# ESP32.net
KiCad netlist of a schematic drawn in Altium Designer
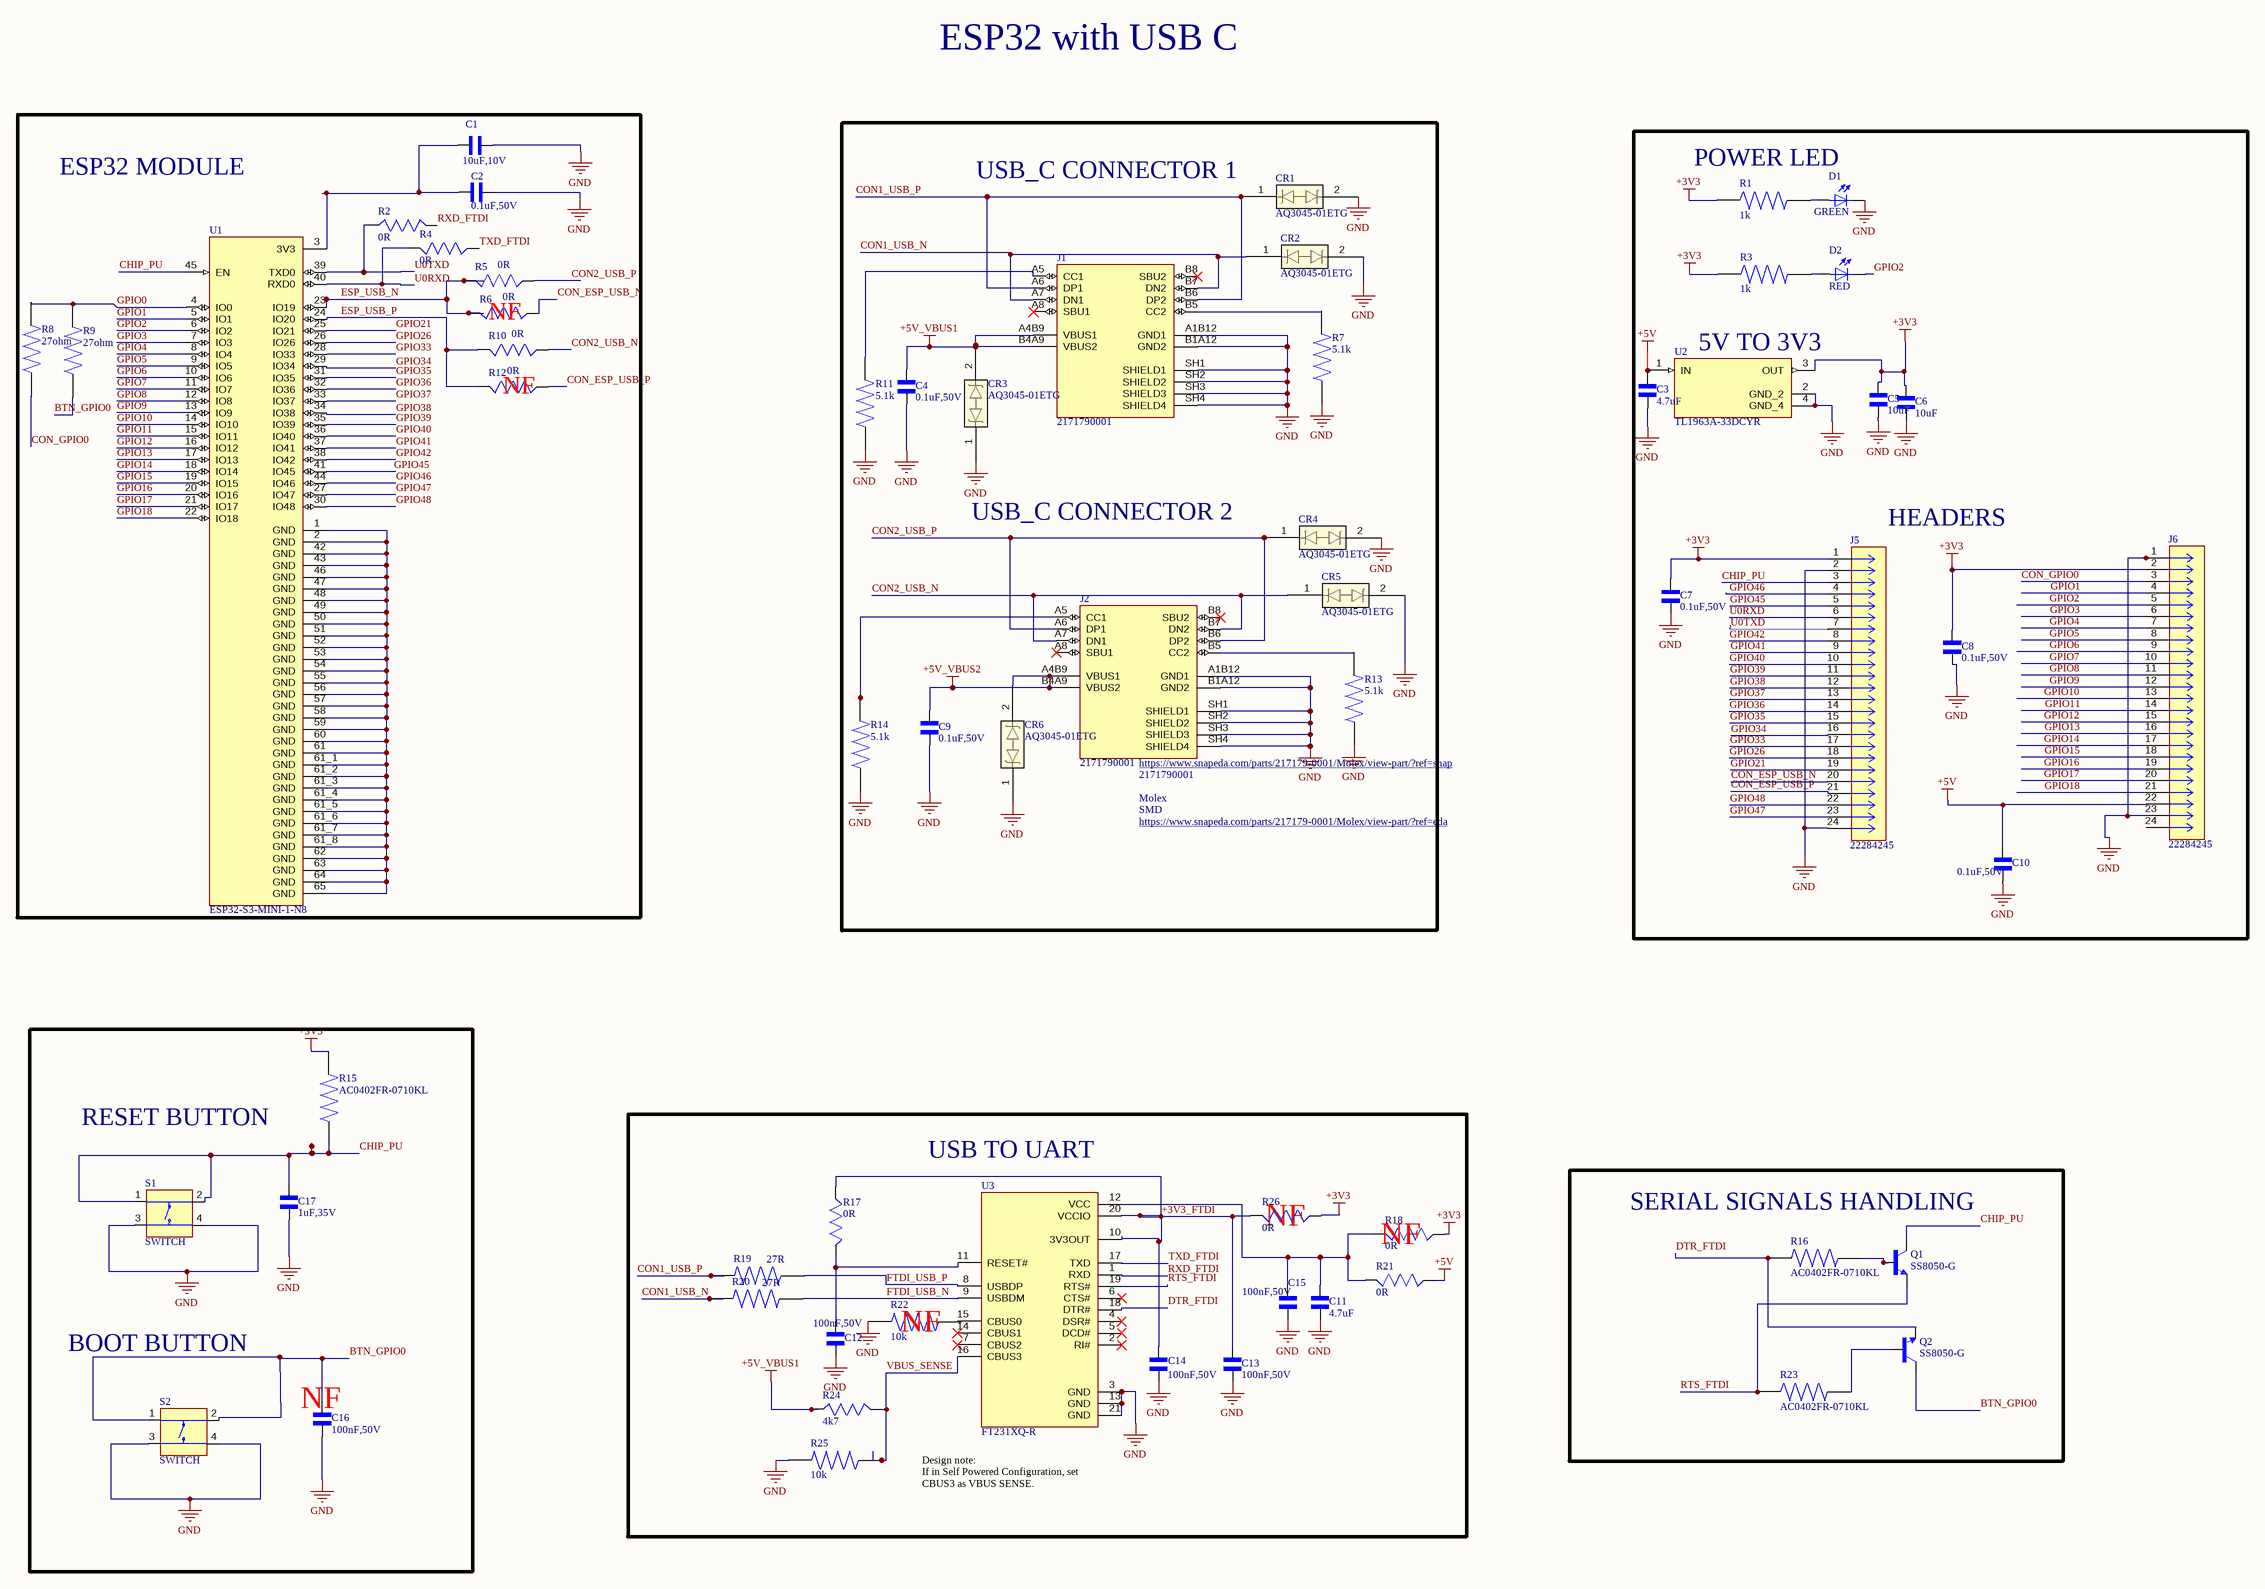
[diagram p0: ESP32.SchDoc]

(export (version "E")
  (design (tool "Eeschema 10.0.6"))
  (components
    (comp (ref "C1")
      (value "10uF,10V")
      (footprint "CAPC1005X90N")
      (description "10 ÂµF Â±20% 10V Ceramic Capacitor X5R 0402 (1005 Metric)")
      (fields (field (name "MF") "Samsung Electro-Mechanics") (field (name "MP") "CL05A106MP8NUB8"))
      (libsource (lib "") (part "CL05A106MP8NUB8_1"))
    )
    (comp (ref "C2")
      (value "0.1uF,50V")
      (footprint "CAPC1005X55N")
      (description "0.1 ÂµF Â±10% 50V Ceramic Capacitor X7R 0402 (1005 Metric)")
      (fields (field (name "MF") "Samsung Electro-Mechanics") (field (name "MP") "CL05B104KB5NNNC"))
      (libsource (lib "") (part "CL05B104KB5NNNC_1"))
    )
    (comp (ref "C3")
      (value "4.7uF")
      (footprint "CAPC1005X55N")
      (description "4.7 ÂµF Â±20% 16V Ceramic Capacitor X5R 0402 (1005 Metric)")
      (fields (field (name "MF") "Samsung Electro-Mechanics") (field (name "MP") "CL05A475MO5LUNC"))
      (libsource (lib "47uF") (part "CL05A475MO5LUNC"))
    )
    (comp (ref "C4")
      (value "0.1uF,50V")
      (footprint "CAPC1005X55N")
      (description "0.1 ÂµF Â±10% 50V Ceramic Capacitor X7R 0402 (1005 Metric)")
      (fields (field (name "MF") "Samsung Electro-Mechanics") (field (name "MP") "CL05B104KB5NNNC"))
      (libsource (lib "0.1uF,50V,0402") (part "CL05B104KB5NNNC"))
    )
    (comp (ref "C5")
      (value "10uF")
      (footprint "CAPC1005X90N")
      (description "10 ÂµF Â±20% 10V Ceramic Capacitor X5R 0402 (1005 Metric)")
      (fields (field (name "MF") "Samsung Electro-Mechanics") (field (name "MP") "CL05A106MP8NUB8"))
      (libsource (lib "10uF,10V,0402") (part "CL05A106MP8NUB8"))
    )
    (comp (ref "C6")
      (value "10uF")
      (footprint "CAPC1005X90N")
      (description "10 ÂµF Â±20% 10V Ceramic Capacitor X5R 0402 (1005 Metric)")
      (fields (field (name "MF") "Samsung Electro-Mechanics") (field (name "MP") "CL05A106MP8NUB8"))
      (libsource (lib "10uF,10V,0402") (part "CL05A106MP8NUB8"))
    )
    (comp (ref "C7")
      (value "0.1uF,50V")
      (footprint "CAPC1005X55N")
      (description "0.1 ÂµF Â±10% 50V Ceramic Capacitor X7R 0402 (1005 Metric)")
      (fields (field (name "MF") "Samsung Electro-Mechanics") (field (name "MP") "CL05B104KB5NNNC"))
      (libsource (lib "0.1uF,50V,0402") (part "CL05B104KB5NNNC"))
    )
    (comp (ref "C8")
      (value "0.1uF,50V")
      (footprint "CAPC1005X55N")
      (description "0.1 ÂµF Â±10% 50V Ceramic Capacitor X7R 0402 (1005 Metric)")
      (fields (field (name "MF") "Samsung Electro-Mechanics") (field (name "MP") "CL05B104KB5NNNC"))
      (libsource (lib "0.1uF,50V,0402") (part "CL05B104KB5NNNC"))
    )
    (comp (ref "C9")
      (value "0.1uF,50V")
      (footprint "CAPC1005X55N")
      (description "0.1 ÂµF Â±10% 50V Ceramic Capacitor X7R 0402 (1005 Metric)")
      (fields (field (name "MF") "Samsung Electro-Mechanics") (field (name "MP") "CL05B104KB5NNNC"))
      (libsource (lib "0.1uF,50V,0402") (part "CL05B104KB5NNNC"))
    )
    (comp (ref "C10")
      (value "0.1uF,50V")
      (footprint "CAPC1005X55N")
      (description "0.1 ÂµF Â±10% 50V Ceramic Capacitor X7R 0402 (1005 Metric)")
      (fields (field (name "MF") "Samsung Electro-Mechanics") (field (name "MP") "CL05B104KB5NNNC"))
      (libsource (lib "0.1uF,50V,0402") (part "CL05B104KB5NNNC"))
    )
    (comp (ref "C11")
      (value "4.7uF")
      (footprint "CAPC1005X55N")
      (description "4.7 ÂµF Â±20% 16V Ceramic Capacitor X5R 0402 (1005 Metric)")
      (fields (field (name "MF") "Samsung Electro-Mechanics") (field (name "MP") "CL05A475MO5LUNC"))
      (libsource (lib "47uF") (part "CL05A475MO5LUNC"))
    )
    (comp (ref "C12")
      (value "100nF,50V")
      (footprint "CAPC1005X55N")
      (description "0.1 ÂµF Â±10% 50V Ceramic Capacitor X7R 0402 (1005 Metric)")
      (fields (field (name "MF") "Samsung Electro-Mechanics") (field (name "MP") "CL05B104KB5NNNC"))
      (libsource (lib "0.1uF,50V,0402") (part "CL05B104KB5NNNC"))
    )
    (comp (ref "C13")
      (value "100nF,50V")
      (footprint "CAPC1005X55N")
      (description "0.1 ÂµF Â±10% 50V Ceramic Capacitor X7R 0402 (1005 Metric)")
      (fields (field (name "MF") "Samsung Electro-Mechanics") (field (name "MP") "CL05B104KB5NNNC"))
      (libsource (lib "0.1uF,50V,0402") (part "CL05B104KB5NNNC"))
    )
    (comp (ref "C14")
      (value "100nF,50V")
      (footprint "CAPC1005X55N")
      (description "0.1 ÂµF Â±10% 50V Ceramic Capacitor X7R 0402 (1005 Metric)")
      (fields (field (name "MF") "Samsung Electro-Mechanics") (field (name "MP") "CL05B104KB5NNNC"))
      (libsource (lib "0.1uF,50V,0402") (part "CL05B104KB5NNNC"))
    )
    (comp (ref "C15")
      (value "100nF,50V")
      (footprint "CAPC1005X55N")
      (description "0.1 ÂµF Â±10% 50V Ceramic Capacitor X7R 0402 (1005 Metric)")
      (fields (field (name "MF") "Samsung Electro-Mechanics") (field (name "MP") "CL05B104KB5NNNC"))
      (libsource (lib "0.1uF,50V,0402") (part "CL05B104KB5NNNC"))
    )
    (comp (ref "C16")
      (value "100nF,50V")
      (footprint "CAPC1005X55N")
      (description "0.1 ÂµF Â±10% 50V Ceramic Capacitor X7R 0402 (1005 Metric)")
      (fields (field (name "MF") "Samsung Electro-Mechanics") (field (name "MP") "CL05B104KB5NNNC"))
      (libsource (lib "0.1uF,50V,0402") (part "CL05B104KB5NNNC"))
    )
    (comp (ref "C17")
      (value "1uF,35V")
      (footprint "CAPC1005X65N")
      (description "1 ÂµF Â±10% 35V Ceramic Capacitor X5R 0402 (1005 Metric)")
      (fields (field (name "MF") "Samsung") (field (name "MP") "CL05A105KL5NRNC"))
      (libsource (lib "1uF,35V,0402") (part "CL05A105KL5NRNC"))
    )
    (comp (ref "CR1")
      (value "AQ3045-01ETG")
      (footprint "RTVS_SOD882_LTF")
      (description "Description")
      (fields (field (name "COPYRIGHT") "Copyright (C) 2025 Ultra Librarian. All rights reserved."))
      (libsource (lib "AQ3045-01ETG") (part "AQ3045-01ETG"))
    )
    (comp (ref "CR2")
      (value "AQ3045-01ETG")
      (footprint "RTVS_SOD882_LTF")
      (description "Description")
      (fields (field (name "COPYRIGHT") "Copyright (C) 2025 Ultra Librarian. All rights reserved."))
      (libsource (lib "AQ3045-01ETG") (part "AQ3045-01ETG"))
    )
    (comp (ref "CR3")
      (value "AQ3045-01ETG")
      (footprint "RTVS_SOD882_LTF")
      (description "Description")
      (fields (field (name "COPYRIGHT") "Copyright (C) 2025 Ultra Librarian. All rights reserved."))
      (libsource (lib "") (part "AQ3045-01ETG_1"))
    )
    (comp (ref "CR4")
      (value "AQ3045-01ETG")
      (footprint "RTVS_SOD882_LTF")
      (description "Description")
      (fields (field (name "COPYRIGHT") "Copyright (C) 2025 Ultra Librarian. All rights reserved."))
      (libsource (lib "AQ3045-01ETG") (part "AQ3045-01ETG"))
    )
    (comp (ref "CR5")
      (value "AQ3045-01ETG")
      (footprint "RTVS_SOD882_LTF")
      (description "Description")
      (fields (field (name "COPYRIGHT") "Copyright (C) 2025 Ultra Librarian. All rights reserved."))
      (libsource (lib "AQ3045-01ETG") (part "AQ3045-01ETG"))
    )
    (comp (ref "CR6")
      (value "AQ3045-01ETG")
      (footprint "RTVS_SOD882_LTF")
      (description "Description")
      (fields (field (name "COPYRIGHT") "Copyright (C) 2025 Ultra Librarian. All rights reserved."))
      (libsource (lib "") (part "AQ3045-01ETG_1"))
    )
    (comp (ref "D1")
      (value "GREEN")
      (footprint "LEDC1005X35N")
      (description "Yellow-Green 571nm LED Indication - Discrete 2V 0402 (1005 Metric)")
      (fields (field (name "MF") "Vishay") (field (name "MP") "VLMG1500-GS08"))
      (libsource (lib "GREEN LED") (part "VLMG1500-GS08"))
    )
    (comp (ref "D2")
      (value "RED")
      (footprint "LEDC1005X35N")
      (description "Yellow-Green 571nm LED Indication - Discrete 2V 0402 (1005 Metric)")
      (fields (field (name "MF") "Vishay") (field (name "MP") "VLMG1500-GS08"))
      (libsource (lib "GREEN LED") (part "VLMG1500-GS08"))
    )
    (comp (ref "J1")
      (value "2171790001")
      (footprint "MOLEX_2171790001")
      (description "USB Type C - Connector, Top-mount SMT, 16pos ¦ Molex Incorporated 217179-0001")
      (fields (field (name "JLCPCB PART #") "C3197684") (field (name "MANUFACTURER") "Molex"))
      (libsource (lib "USB C") (part "2171790001"))
    )
    (comp (ref "J2")
      (value "2171790001")
      (footprint "MOLEX_2171790001")
      (description "USB Type C - Connector, Top-mount SMT, 16pos ¦ Molex Incorporated 217179-0001")
      (fields
        (field (name "SNAPEDA_LINK") "https://www.snapeda.com/parts/217179-0001/Molex/view-part/?ref=snap")
        (field (name "MANUFACTURER PART #") "2171790001")
        (field (name "JLCPCB PART #") "C3197684")
        (field (name "MANUFACTURER") "Molex")
        (field (name "PACKAGE") "SMD")
        (field (name "CHECK_PRICES") "https://www.snapeda.com/parts/217179-0001/Molex/view-part/?ref=eda")
      )
      (libsource (lib "USB C") (part "2171790001"))
    )
    (comp (ref "J5")
      (value "22284245")
      (footprint "CONN_SD-42375-001_M295_24_MOL")
      (description "Connector Header Through Hole 24 position 0.100 (2.54mm)")
      (fields (field (name "MF") "Molex") (field (name "MP") "22-28-4245"))
      (libsource (lib "24 PIN HEADERS") (part "22284245"))
    )
    (comp (ref "J6")
      (value "22284245")
      (footprint "CONN_SD-42375-001_M295_24_MOL")
      (description "Connector Header Through Hole 24 position 0.100 (2.54mm)")
      (fields (field (name "MF") "Molex") (field (name "MP") "22-28-4245"))
      (libsource (lib "24 PIN HEADERS") (part "22284245"))
    )
    (comp (ref "Q1")
      (value "SS8050-G")
      (footprint "TRANS_SS8050-G")
      (description "Bipolar (BJT) Transistor NPN 25 V 1.5 A 100MHz 300 mW Surface Mount SOT-23-3")
      (fields (field (name "DIGI-KEY_PART_NUMBER") "641-1790-2-ND") (field (name "MP") "SS8050G"))
      (libsource (lib "") (part "SS8050-G_1"))
    )
    (comp (ref "Q2")
      (value "SS8050-G")
      (footprint "TRANS_SS8050-G")
      (description "Bipolar (BJT) Transistor NPN 25 V 1.5 A 100MHz 300 mW Surface Mount SOT-23-3")
      (fields (field (name "DIGI-KEY_PART_NUMBER") "641-1790-2-ND") (field (name "MP") "SS8050G"))
      (libsource (lib "SS8050-G") (part "SS8050-G"))
    )
    (comp (ref "R1")
      (value "1k")
      (footprint "RESC1005X40N")
      (description "1 kOhms Â±1% 0.063W, 1/16W Chip Resistor 0402 (1005 Metric) Moisture Resistant Thick Film")
      (fields (field (name "MF") "Yageo Corporation") (field (name "MP") "RC0402FR071KL"))
      (libsource (lib "1kR") (part "RC0402FR-071KL"))
    )
    (comp (ref "R2")
      (value "0R")
      (footprint "RESC1005X40")
      (description "0 Ohms Jumper 0.063W, 1/16W Chip Resistor 0402 (1005 Metric) Moisture Resistant Thick Film")
      (fields (field (name "MF") "Yageo") (field (name "DIGI-KEY_PART_NUMBER") "311-0.0JRTR-ND"))
      (libsource (lib "0R") (part "RC0402JR-070RL"))
    )
    (comp (ref "R3")
      (value "1k")
      (footprint "RESC1005X40N")
      (description "1 kOhms Â±1% 0.063W, 1/16W Chip Resistor 0402 (1005 Metric) Moisture Resistant Thick Film")
      (fields (field (name "MF") "Yageo Corporation") (field (name "MP") "RC0402FR071KL"))
      (libsource (lib "1kR") (part "RC0402FR-071KL"))
    )
    (comp (ref "R4")
      (value "0R")
      (footprint "RESC1005X40")
      (description "0 Ohms Jumper 0.063W, 1/16W Chip Resistor 0402 (1005 Metric) Moisture Resistant Thick Film")
      (fields (field (name "MF") "Yageo") (field (name "DIGI-KEY_PART_NUMBER") "311-0.0JRTR-ND"))
      (libsource (lib "0R") (part "RC0402JR-070RL"))
    )
    (comp (ref "R5")
      (value "0R")
      (footprint "RESC1005X40")
      (description "0 Ohms Jumper 0.063W, 1/16W Chip Resistor 0402 (1005 Metric) Moisture Resistant Thick Film")
      (fields (field (name "MF") "Yageo") (field (name "DIGI-KEY_PART_NUMBER") "311-0.0JRTR-ND"))
      (libsource (lib "0R") (part "RC0402JR-070RL"))
    )
    (comp (ref "R6")
      (value "0R")
      (footprint "RESC1005X40")
      (description "0 Ohms Jumper 0.063W, 1/16W Chip Resistor 0402 (1005 Metric) Moisture Resistant Thick Film")
      (fields (field (name "MF") "Yageo") (field (name "DIGI-KEY_PART_NUMBER") "311-0.0JRTR-ND"))
      (libsource (lib "0R") (part "RC0402JR-070RL"))
    )
    (comp (ref "R7")
      (value "5.1k")
      (footprint "RESC1005X40N")
      (description "27 Ohms Â±1% 0.063W, 1/16W Chip Resistor 0402 (1005 Metric) Moisture Resistant Thick Film")
      (fields (field (name "MF") "Yageo") (field (name "MP") "RC0402FR-0727RL"))
      (libsource (lib "5.1k Ohm (2)") (part "RC0402FR-0727RL"))
    )
    (comp (ref "R8")
      (value "27ohm")
      (footprint "RESC1005X40N")
      (description "27 Ohms Â±1% 0.063W, 1/16W Chip Resistor 0402 (1005 Metric) Moisture Resistant Thick Film")
      (fields (field (name "MF") "Yageo") (field (name "MP") "RC0402FR-0727RL"))
      (libsource (lib "27ohm,0402") (part "RC0402FR-0727RL"))
    )
    (comp (ref "R9")
      (value "27ohm")
      (footprint "RESC1005X40N")
      (description "27 Ohms Â±1% 0.063W, 1/16W Chip Resistor 0402 (1005 Metric) Moisture Resistant Thick Film")
      (fields (field (name "MF") "Yageo") (field (name "MP") "RC0402FR-0727RL"))
      (libsource (lib "27ohm,0402") (part "RC0402FR-0727RL"))
    )
    (comp (ref "R10")
      (value "0R")
      (footprint "RESC1005X40")
      (description "0 Ohms Jumper 0.063W, 1/16W Chip Resistor 0402 (1005 Metric) Moisture Resistant Thick Film")
      (fields (field (name "MF") "Yageo") (field (name "DIGI-KEY_PART_NUMBER") "311-0.0JRTR-ND"))
      (libsource (lib "0R") (part "RC0402JR-070RL"))
    )
    (comp (ref "R11")
      (value "5.1k")
      (footprint "RESC1005X40N")
      (description "27 Ohms Â±1% 0.063W, 1/16W Chip Resistor 0402 (1005 Metric) Moisture Resistant Thick Film")
      (fields (field (name "MF") "Yageo") (field (name "MP") "RC0402FR-0727RL"))
      (libsource (lib "5.1k Ohm (2)") (part "RC0402FR-0727RL"))
    )
    (comp (ref "R12")
      (value "0R")
      (footprint "RESC1005X40")
      (description "0 Ohms Jumper 0.063W, 1/16W Chip Resistor 0402 (1005 Metric) Moisture Resistant Thick Film")
      (fields (field (name "MF") "Yageo") (field (name "DIGI-KEY_PART_NUMBER") "311-0.0JRTR-ND"))
      (libsource (lib "0R") (part "RC0402JR-070RL"))
    )
    (comp (ref "R13")
      (value "5.1k")
      (footprint "RESC1005X40N")
      (description "27 Ohms Â±1% 0.063W, 1/16W Chip Resistor 0402 (1005 Metric) Moisture Resistant Thick Film")
      (fields (field (name "MF") "Yageo") (field (name "MP") "RC0402FR-0727RL"))
      (libsource (lib "5.1k Ohm (2)") (part "RC0402FR-0727RL"))
    )
    (comp (ref "R14")
      (value "5.1k")
      (footprint "RESC1005X40N")
      (description "27 Ohms Â±1% 0.063W, 1/16W Chip Resistor 0402 (1005 Metric) Moisture Resistant Thick Film")
      (fields (field (name "MF") "Yageo") (field (name "MP") "RC0402FR-0727RL"))
      (libsource (lib "5.1k Ohm (2)") (part "RC0402FR-0727RL"))
    )
    (comp (ref "R15")
      (value "AC0402FR-0710KL")
      (footprint "RESC1005X37N")
      (fields (field (name "DIGI-KEY_PART_NUMBER") "YAG3436TR-ND") (field (name "MF") "Yageo"))
      (libsource (lib "10k ohm") (part "AC0402FR-0710KL"))
    )
    (comp (ref "R16")
      (value "AC0402FR-0710KL")
      (footprint "RESC1005X37N")
      (fields (field (name "DIGI-KEY_PART_NUMBER") "YAG3436TR-ND") (field (name "MF") "Yageo"))
      (libsource (lib "10k ohm") (part "AC0402FR-0710KL"))
    )
    (comp (ref "R17")
      (value "0R")
      (footprint "RESC1005X40")
      (description "0 Ohms Jumper 0.063W, 1/16W Chip Resistor 0402 (1005 Metric) Moisture Resistant Thick Film")
      (fields (field (name "MF") "Yageo") (field (name "DIGI-KEY_PART_NUMBER") "311-0.0JRTR-ND"))
      (libsource (lib "0R") (part "RC0402JR-070RL"))
    )
    (comp (ref "R18")
      (value "0R")
      (footprint "RESC1005X40")
      (description "0 Ohms Jumper 0.063W, 1/16W Chip Resistor 0402 (1005 Metric) Moisture Resistant Thick Film")
      (fields (field (name "MF") "Yageo") (field (name "DIGI-KEY_PART_NUMBER") "311-0.0JRTR-ND"))
      (libsource (lib "0R") (part "RC0402JR-070RL"))
    )
    (comp (ref "R19")
      (value "27R")
      (footprint "RESC1005X40N")
      (description "27 Ohms Â±1% 0.063W, 1/16W Chip Resistor 0402 (1005 Metric) Moisture Resistant Thick Film")
      (fields (field (name "MF") "Yageo") (field (name "MP") "RC0402FR-0727RL"))
      (libsource (lib "27ohm,0402") (part "RC0402FR-0727RL"))
    )
    (comp (ref "R20")
      (value "27R")
      (footprint "RESC1005X40N")
      (description "27 Ohms Â±1% 0.063W, 1/16W Chip Resistor 0402 (1005 Metric) Moisture Resistant Thick Film")
      (fields (field (name "MF") "Yageo") (field (name "MP") "RC0402FR-0727RL"))
      (libsource (lib "27ohm,0402") (part "RC0402FR-0727RL"))
    )
    (comp (ref "R21")
      (value "0R")
      (footprint "RESC1005X40")
      (description "0 Ohms Jumper 0.063W, 1/16W Chip Resistor 0402 (1005 Metric) Moisture Resistant Thick Film")
      (fields (field (name "MF") "Yageo") (field (name "DIGI-KEY_PART_NUMBER") "311-0.0JRTR-ND"))
      (libsource (lib "0R") (part "RC0402JR-070RL"))
    )
    (comp (ref "R22")
      (value "10k")
      (footprint "RESC1005X37N")
      (fields
        (field (name "MP") "AC0402FR-0710KL")
        (field (name "DIGI-KEY_PART_NUMBER") "YAG3436TR-ND")
        (field (name "MF") "Yageo")
      )
      (libsource (lib "10k ohm") (part "AC0402FR-0710KL"))
    )
    (comp (ref "R23")
      (value "AC0402FR-0710KL")
      (footprint "RESC1005X37N")
      (fields (field (name "DIGI-KEY_PART_NUMBER") "YAG3436TR-ND") (field (name "MF") "Yageo"))
      (libsource (lib "10k ohm") (part "AC0402FR-0710KL"))
    )
    (comp (ref "R24")
      (value "4k7")
      (footprint "RESC1005X40")
      (description "4.7 kOhms Â±1% 0.063W, 1/16W Chip Resistor 0402 (1005 Metric) Moisture Resistant Thick Film")
      (fields (field (name "MF") "Yageo") (field (name "MP") "RC0402FR-074K7L"))
      (libsource (lib "4.7k ohm") (part "RC0402FR-074K7L"))
    )
    (comp (ref "R25")
      (value "10k")
      (footprint "RESC1005X37N")
      (fields
        (field (name "MP") "AC0402FR-0710KL")
        (field (name "DIGI-KEY_PART_NUMBER") "YAG3436TR-ND")
        (field (name "MF") "Yageo")
      )
      (libsource (lib "10k ohm") (part "AC0402FR-0710KL"))
    )
    (comp (ref "R26")
      (value "0R")
      (footprint "RESC1005X40")
      (description "0 Ohms Jumper 0.063W, 1/16W Chip Resistor 0402 (1005 Metric) Moisture Resistant Thick Film")
      (fields (field (name "MF") "Yageo") (field (name "DIGI-KEY_PART_NUMBER") "311-0.0JRTR-ND"))
      (libsource (lib "0R") (part "RC0402JR-070RL"))
    )
    (comp (ref "S1")
      (value "SWITCH")
      (footprint "SWITCH_43SMTR92LFS")
      (fields (field (name "MF") "C&K") (field (name "MP") "PTS645SK50SMTR92 LFS"))
      (libsource (lib "Tactile switch") (part "PTS645SK50SMTR92LFS"))
    )
    (comp (ref "S2")
      (value "SWITCH")
      (footprint "SWITCH_43SMTR92LFS")
      (fields (field (name "MF") "C&K") (field (name "MP") "PTS645SK50SMTR92 LFS"))
      (libsource (lib "Tactile switch") (part "PTS645SK50SMTR92LFS"))
    )
    (comp (ref "U1")
      (value "ESP32-S3-MINI-1-N8")
      (footprint "XCVR_ESP32-S3-MINI-1-N8")
      (fields (field (name "MANUFACTURER") "Espressif Systems") (field (name "JLCPCB PART #") "C2913206"))
      (libsource (lib "ESP32-S3-MINI-1-N8") (part "ESP32-S3-MINI-1-N8"))
    )
    (comp (ref "U2")
      (value "TL1963A-33DCYR")
      (footprint "VREG_TL1963A-33DCYR")
      (description "1.5-A, 20-V, low-dropout voltage regulator with reverse current & reverse voltage protection")
      (fields (field (name "MF") "Texas Instruments"))
      (libsource (lib "LDO") (part "TL1963A-33DCYR"))
    )
    (comp (ref "U3")
      (value "FT231XQ-R")
      (footprint "QFN50P400X400X80-21N")
      (description "USB2.0 Full Speed IC offers a compact bridge to full handshake UART Interface")
      (libsource (lib "USB_to_UART") (part "FT231XQ-R"))
    )
  )
  (nets
    (net (code "1") (name "+3V3") (class "Default")
      (node (ref "C5") (pin "2") (pinfunction "2_2") (pintype "passive"))
      (node (ref "C6") (pin "2") (pinfunction "2_2") (pintype "passive"))
      (node (ref "C7") (pin "2") (pinfunction "2_2") (pintype "passive"))
      (node (ref "C8") (pin "2") (pinfunction "2_2") (pintype "passive"))
      (node (ref "J5") (pin "1") (pinfunction "1_1") (pintype "passive"))
      (node (ref "J6") (pin "2") (pinfunction "2_2") (pintype "passive"))
      (node (ref "R1") (pin "1") (pinfunction "1_1") (pintype "passive"))
      (node (ref "R15") (pin "2") (pinfunction "2_2") (pintype "passive"))
      (node (ref "R18") (pin "2") (pinfunction "2_2") (pintype "passive"))
      (node (ref "R26") (pin "2") (pinfunction "2_2") (pintype "passive"))
      (node (ref "R3") (pin "1") (pinfunction "1_1") (pintype "passive"))
      (node (ref "U2") (pin "3") (pinfunction "OUT_3") (pintype "output"))
    )
    (net (code "2") (name "+5V") (class "Default")
      (node (ref "C10") (pin "2") (pinfunction "2_2") (pintype "passive"))
      (node (ref "C3") (pin "2") (pinfunction "2_2") (pintype "passive"))
      (node (ref "J6") (pin "22") (pinfunction "22_22") (pintype "passive"))
      (node (ref "R21") (pin "2") (pinfunction "2_2") (pintype "passive"))
      (node (ref "U2") (pin "1") (pinfunction "IN_1") (pintype "input"))
    )
    (net (code "3") (name "+5V_VBUS1") (class "Default")
      (node (ref "C4") (pin "2") (pinfunction "2_2") (pintype "passive"))
      (node (ref "CR3") (pin "2") (pinfunction "2_2") (pintype "passive"))
      (node (ref "J1") (pin "A4B9") (pinfunction "VBUS1_A4B9") (pintype "power_in"))
      (node (ref "J1") (pin "B4A9") (pinfunction "VBUS2_B4A9") (pintype "power_in"))
      (node (ref "R24") (pin "2") (pinfunction "2_2") (pintype "passive"))
    )
    (net (code "4") (name "+5V_VBUS2") (class "Default")
      (node (ref "C9") (pin "2") (pinfunction "2_2") (pintype "passive"))
      (node (ref "CR6") (pin "2") (pinfunction "2_2") (pintype "passive"))
      (node (ref "J2") (pin "A4B9") (pinfunction "VBUS1_A4B9") (pintype "power_in"))
      (node (ref "J2") (pin "B4A9") (pinfunction "VBUS2_B4A9") (pintype "power_in"))
    )
    (net (code "5") (name "/+3V3_FTDI") (class "Default")
      (node (ref "C13") (pin "2") (pinfunction "2_2") (pintype "passive"))
      (node (ref "C14") (pin "2") (pinfunction "2_2") (pintype "passive"))
      (node (ref "R17") (pin "2") (pinfunction "2_2") (pintype "passive"))
      (node (ref "R26") (pin "1") (pinfunction "1_1") (pintype "passive"))
      (node (ref "U3") (pin "10") (pinfunction "3V3OUT_10") (pintype "passive"))
      (node (ref "U3") (pin "20") (pinfunction "VCCIO_20") (pintype "passive"))
    )
    (net (code "6") (name "/BTN_GPIO0") (class "Default")
      (node (ref "C16") (pin "2") (pinfunction "2_2") (pintype "passive"))
      (node (ref "Q2") (pin "3") (pinfunction "C_3") (pintype "passive"))
      (node (ref "R9") (pin "1") (pinfunction "1_1") (pintype "passive"))
      (node (ref "S2") (pin "1") (pinfunction "1_1") (pintype "passive"))
      (node (ref "S2") (pin "2") (pinfunction "2_2") (pintype "passive"))
    )
    (net (code "7") (name "/CHIP_PU") (class "Default")
      (node (ref "C17") (pin "1") (pinfunction "1_1") (pintype "passive"))
      (node (ref "J5") (pin "3") (pinfunction "3_3") (pintype "passive"))
      (node (ref "Q1") (pin "3") (pinfunction "C_3") (pintype "passive"))
      (node (ref "R15") (pin "1") (pinfunction "1_1") (pintype "passive"))
      (node (ref "S1") (pin "1") (pinfunction "1_1") (pintype "passive"))
      (node (ref "S1") (pin "2") (pinfunction "2_2") (pintype "passive"))
      (node (ref "U1") (pin "45") (pinfunction "EN_45") (pintype "input"))
    )
    (net (code "8") (name "/CON1_USB_N") (class "Default")
      (node (ref "CR2") (pin "1") (pinfunction "1_1") (pintype "passive"))
      (node (ref "J1") (pin "A7") (pinfunction "DN1_A7") (pintype "bidirectional"))
      (node (ref "J1") (pin "B7") (pinfunction "DN2_B7") (pintype "bidirectional"))
      (node (ref "R20") (pin "1") (pinfunction "1_1") (pintype "passive"))
    )
    (net (code "9") (name "/CON1_USB_P") (class "Default")
      (node (ref "CR1") (pin "1") (pinfunction "1_1") (pintype "passive"))
      (node (ref "J1") (pin "A6") (pinfunction "DP1_A6") (pintype "bidirectional"))
      (node (ref "J1") (pin "B6") (pinfunction "DP2_B6") (pintype "bidirectional"))
      (node (ref "R19") (pin "1") (pinfunction "1_1") (pintype "passive"))
    )
    (net (code "10") (name "/CON2_USB_N") (class "Default")
      (node (ref "CR5") (pin "1") (pinfunction "1_1") (pintype "passive"))
      (node (ref "J2") (pin "A7") (pinfunction "DN1_A7") (pintype "bidirectional"))
      (node (ref "J2") (pin "B7") (pinfunction "DN2_B7") (pintype "bidirectional"))
      (node (ref "R10") (pin "2") (pinfunction "2_2") (pintype "passive"))
    )
    (net (code "11") (name "/CON2_USB_P") (class "Default")
      (node (ref "CR4") (pin "1") (pinfunction "1_1") (pintype "passive"))
      (node (ref "J2") (pin "A6") (pinfunction "DP1_A6") (pintype "bidirectional"))
      (node (ref "J2") (pin "B6") (pinfunction "DP2_B6") (pintype "bidirectional"))
      (node (ref "R5") (pin "2") (pinfunction "2_2") (pintype "passive"))
    )
    (net (code "12") (name "/CON_ESP_USB_N") (class "Default")
      (node (ref "J5") (pin "20") (pinfunction "20_20") (pintype "passive"))
      (node (ref "R6") (pin "2") (pinfunction "2_2") (pintype "passive"))
    )
    (net (code "13") (name "/CON_ESP_USB_P") (class "Default")
      (node (ref "J5") (pin "21") (pinfunction "21_21") (pintype "passive"))
      (node (ref "R12") (pin "2") (pinfunction "2_2") (pintype "passive"))
    )
    (net (code "14") (name "/CON_GPIO0") (class "Default")
      (node (ref "J6") (pin "3") (pinfunction "3_3") (pintype "passive"))
      (node (ref "R8") (pin "1") (pinfunction "1_1") (pintype "passive"))
    )
    (net (code "15") (name "/DTR_FTDI") (class "Default")
      (node (ref "Q2") (pin "2") (pinfunction "E_2") (pintype "passive"))
      (node (ref "R16") (pin "1") (pinfunction "1_1") (pintype "passive"))
      (node (ref "U3") (pin "18") (pinfunction "DTR#_18") (pintype "passive"))
    )
    (net (code "16") (name "/ESP_USB_N") (class "Default")
      (node (ref "R5") (pin "1") (pinfunction "1_1") (pintype "passive"))
      (node (ref "R6") (pin "1") (pinfunction "1_1") (pintype "passive"))
      (node (ref "U1") (pin "23") (pinfunction "IO19_23") (pintype "bidirectional"))
    )
    (net (code "17") (name "/ESP_USB_P") (class "Default")
      (node (ref "R10") (pin "1") (pinfunction "1_1") (pintype "passive"))
      (node (ref "R12") (pin "1") (pinfunction "1_1") (pintype "passive"))
      (node (ref "U1") (pin "24") (pinfunction "IO20_24") (pintype "bidirectional"))
    )
    (net (code "18") (name "/FTDI_USB_N") (class "Default")
      (node (ref "R20") (pin "2") (pinfunction "2_2") (pintype "passive"))
      (node (ref "U3") (pin "9") (pinfunction "USBDM_9") (pintype "passive"))
    )
    (net (code "19") (name "/FTDI_USB_P") (class "Default")
      (node (ref "R19") (pin "2") (pinfunction "2_2") (pintype "passive"))
      (node (ref "U3") (pin "8") (pinfunction "USBDP_8") (pintype "passive"))
    )
    (net (code "20") (name "/GPIO0") (class "Default")
      (node (ref "R8") (pin "2") (pinfunction "2_2") (pintype "passive"))
      (node (ref "R9") (pin "2") (pinfunction "2_2") (pintype "passive"))
      (node (ref "U1") (pin "4") (pinfunction "IO0_4") (pintype "bidirectional"))
    )
    (net (code "21") (name "/GPIO1") (class "Default")
      (node (ref "J6") (pin "4") (pinfunction "4_4") (pintype "passive"))
      (node (ref "U1") (pin "5") (pinfunction "IO1_5") (pintype "bidirectional"))
    )
    (net (code "22") (name "/GPIO2") (class "Default")
      (node (ref "D2") (pin "2") (pinfunction "2_2") (pintype "passive"))
      (node (ref "J6") (pin "5") (pinfunction "5_5") (pintype "passive"))
      (node (ref "U1") (pin "6") (pinfunction "IO2_6") (pintype "bidirectional"))
    )
    (net (code "23") (name "/GPIO3") (class "Default")
      (node (ref "J6") (pin "6") (pinfunction "6_6") (pintype "passive"))
      (node (ref "U1") (pin "7") (pinfunction "IO3_7") (pintype "bidirectional"))
    )
    (net (code "24") (name "/GPIO4") (class "Default")
      (node (ref "J6") (pin "7") (pinfunction "7_7") (pintype "passive"))
      (node (ref "U1") (pin "8") (pinfunction "IO4_8") (pintype "bidirectional"))
    )
    (net (code "25") (name "/GPIO5") (class "Default")
      (node (ref "J6") (pin "8") (pinfunction "8_8") (pintype "passive"))
      (node (ref "U1") (pin "9") (pinfunction "IO5_9") (pintype "bidirectional"))
    )
    (net (code "26") (name "/GPIO6") (class "Default")
      (node (ref "J6") (pin "9") (pinfunction "9_9") (pintype "passive"))
      (node (ref "U1") (pin "10") (pinfunction "IO6_10") (pintype "bidirectional"))
    )
    (net (code "27") (name "/GPIO7") (class "Default")
      (node (ref "J6") (pin "10") (pinfunction "10_10") (pintype "passive"))
      (node (ref "U1") (pin "11") (pinfunction "IO7_11") (pintype "bidirectional"))
    )
    (net (code "28") (name "/GPIO8") (class "Default")
      (node (ref "J6") (pin "11") (pinfunction "11_11") (pintype "passive"))
      (node (ref "U1") (pin "12") (pinfunction "IO8_12") (pintype "bidirectional"))
    )
    (net (code "29") (name "/GPIO9") (class "Default")
      (node (ref "J6") (pin "12") (pinfunction "12_12") (pintype "passive"))
      (node (ref "U1") (pin "13") (pinfunction "IO9_13") (pintype "bidirectional"))
    )
    (net (code "30") (name "/GPIO10") (class "Default")
      (node (ref "J6") (pin "13") (pinfunction "13_13") (pintype "passive"))
      (node (ref "U1") (pin "14") (pinfunction "IO10_14") (pintype "bidirectional"))
    )
    (net (code "31") (name "/GPIO11") (class "Default")
      (node (ref "J6") (pin "14") (pinfunction "14_14") (pintype "passive"))
      (node (ref "U1") (pin "15") (pinfunction "IO11_15") (pintype "bidirectional"))
    )
    (net (code "32") (name "/GPIO12") (class "Default")
      (node (ref "J6") (pin "15") (pinfunction "15_15") (pintype "passive"))
      (node (ref "U1") (pin "16") (pinfunction "IO12_16") (pintype "bidirectional"))
    )
    (net (code "33") (name "/GPIO13") (class "Default")
      (node (ref "J6") (pin "16") (pinfunction "16_16") (pintype "passive"))
      (node (ref "U1") (pin "17") (pinfunction "IO13_17") (pintype "bidirectional"))
    )
    (net (code "34") (name "/GPIO14") (class "Default")
      (node (ref "J6") (pin "17") (pinfunction "17_17") (pintype "passive"))
      (node (ref "U1") (pin "18") (pinfunction "IO14_18") (pintype "bidirectional"))
    )
    (net (code "35") (name "/GPIO15") (class "Default")
      (node (ref "J6") (pin "18") (pinfunction "18_18") (pintype "passive"))
      (node (ref "U1") (pin "19") (pinfunction "IO15_19") (pintype "bidirectional"))
    )
    (net (code "36") (name "/GPIO16") (class "Default")
      (node (ref "J6") (pin "19") (pinfunction "19_19") (pintype "passive"))
      (node (ref "U1") (pin "20") (pinfunction "IO16_20") (pintype "bidirectional"))
    )
    (net (code "37") (name "/GPIO17") (class "Default")
      (node (ref "J6") (pin "20") (pinfunction "20_20") (pintype "passive"))
      (node (ref "U1") (pin "21") (pinfunction "IO17_21") (pintype "bidirectional"))
    )
    (net (code "38") (name "/GPIO18") (class "Default")
      (node (ref "J6") (pin "21") (pinfunction "21_21") (pintype "passive"))
      (node (ref "U1") (pin "22") (pinfunction "IO18_22") (pintype "bidirectional"))
    )
    (net (code "39") (name "/GPIO21") (class "Default")
      (node (ref "J5") (pin "19") (pinfunction "19_19") (pintype "passive"))
      (node (ref "U1") (pin "25") (pinfunction "IO21_25") (pintype "bidirectional"))
    )
    (net (code "40") (name "/GPIO26") (class "Default")
      (node (ref "J5") (pin "18") (pinfunction "18_18") (pintype "passive"))
      (node (ref "U1") (pin "26") (pinfunction "IO26_26") (pintype "bidirectional"))
    )
    (net (code "41") (name "/GPIO33") (class "Default")
      (node (ref "J5") (pin "17") (pinfunction "17_17") (pintype "passive"))
      (node (ref "U1") (pin "28") (pinfunction "IO33_28") (pintype "bidirectional"))
    )
    (net (code "42") (name "/GPIO34") (class "Default")
      (node (ref "J5") (pin "16") (pinfunction "16_16") (pintype "passive"))
      (node (ref "U1") (pin "29") (pinfunction "IO34_29") (pintype "bidirectional"))
    )
    (net (code "43") (name "/GPIO35") (class "Default")
      (node (ref "J5") (pin "15") (pinfunction "15_15") (pintype "passive"))
      (node (ref "U1") (pin "31") (pinfunction "IO35_31") (pintype "bidirectional"))
    )
    (net (code "44") (name "/GPIO36") (class "Default")
      (node (ref "J5") (pin "14") (pinfunction "14_14") (pintype "passive"))
      (node (ref "U1") (pin "32") (pinfunction "IO36_32") (pintype "bidirectional"))
    )
    (net (code "45") (name "/GPIO37") (class "Default")
      (node (ref "J5") (pin "13") (pinfunction "13_13") (pintype "passive"))
      (node (ref "U1") (pin "33") (pinfunction "IO37_33") (pintype "bidirectional"))
    )
    (net (code "46") (name "/GPIO38") (class "Default")
      (node (ref "J5") (pin "12") (pinfunction "12_12") (pintype "passive"))
      (node (ref "U1") (pin "34") (pinfunction "IO38_34") (pintype "bidirectional"))
    )
    (net (code "47") (name "/GPIO39") (class "Default")
      (node (ref "J5") (pin "11") (pinfunction "11_11") (pintype "passive"))
      (node (ref "U1") (pin "35") (pinfunction "IO39_35") (pintype "bidirectional"))
    )
    (net (code "48") (name "/GPIO40") (class "Default")
      (node (ref "J5") (pin "10") (pinfunction "10_10") (pintype "passive"))
      (node (ref "U1") (pin "36") (pinfunction "IO40_36") (pintype "bidirectional"))
    )
    (net (code "49") (name "/GPIO41") (class "Default")
      (node (ref "J5") (pin "9") (pinfunction "9_9") (pintype "passive"))
      (node (ref "U1") (pin "37") (pinfunction "IO41_37") (pintype "bidirectional"))
    )
    (net (code "50") (name "/GPIO42") (class "Default")
      (node (ref "J5") (pin "8") (pinfunction "8_8") (pintype "passive"))
      (node (ref "U1") (pin "38") (pinfunction "IO42_38") (pintype "bidirectional"))
    )
    (net (code "51") (name "/GPIO45") (class "Default")
      (node (ref "J5") (pin "5") (pinfunction "5_5") (pintype "passive"))
      (node (ref "U1") (pin "41") (pinfunction "IO45_41") (pintype "bidirectional"))
    )
    (net (code "52") (name "/GPIO46") (class "Default")
      (node (ref "J5") (pin "4") (pinfunction "4_4") (pintype "passive"))
      (node (ref "U1") (pin "44") (pinfunction "IO46_44") (pintype "bidirectional"))
    )
    (net (code "53") (name "/GPIO47") (class "Default")
      (node (ref "J5") (pin "23") (pinfunction "23_23") (pintype "passive"))
      (node (ref "U1") (pin "27") (pinfunction "IO47_27") (pintype "bidirectional"))
    )
    (net (code "54") (name "/GPIO48") (class "Default")
      (node (ref "J5") (pin "22") (pinfunction "22_22") (pintype "passive"))
      (node (ref "U1") (pin "30") (pinfunction "IO48_30") (pintype "bidirectional"))
    )
    (net (code "55") (name "/RTS_FTDI") (class "Default")
      (node (ref "Q1") (pin "2") (pinfunction "E_2") (pintype "passive"))
      (node (ref "R23") (pin "1") (pinfunction "1_1") (pintype "passive"))
      (node (ref "U3") (pin "19") (pinfunction "RTS#_19") (pintype "passive"))
    )
    (net (code "56") (name "/RXD_FTDI") (class "Default")
      (node (ref "R2") (pin "1") (pinfunction "1_1") (pintype "passive"))
      (node (ref "U3") (pin "1") (pinfunction "RXD_1") (pintype "passive"))
    )
    (net (code "57") (name "/TXD_FTDI") (class "Default")
      (node (ref "R4") (pin "2") (pinfunction "2_2") (pintype "passive"))
      (node (ref "U3") (pin "17") (pinfunction "TXD_17") (pintype "passive"))
    )
    (net (code "58") (name "/U0RXD") (class "Default")
      (node (ref "J5") (pin "6") (pinfunction "6_6") (pintype "passive"))
      (node (ref "R4") (pin "1") (pinfunction "1_1") (pintype "passive"))
      (node (ref "U1") (pin "40") (pinfunction "RXD0_40") (pintype "bidirectional"))
    )
    (net (code "59") (name "/U0TXD") (class "Default")
      (node (ref "J5") (pin "7") (pinfunction "7_7") (pintype "passive"))
      (node (ref "R2") (pin "2") (pinfunction "2_2") (pintype "passive"))
      (node (ref "U1") (pin "39") (pinfunction "TXD0_39") (pintype "bidirectional"))
    )
    (net (code "60") (name "/VBUS_SENSE") (class "Default")
      (node (ref "R24") (pin "1") (pinfunction "1_1") (pintype "passive"))
      (node (ref "R25") (pin "1") (pinfunction "1_1") (pintype "passive"))
      (node (ref "U3") (pin "16") (pinfunction "CBUS3_16") (pintype "passive"))
    )
    (net (code "61") (name "GND") (class "Default")
      (node (ref "C1") (pin "2") (pinfunction "2_2") (pintype "passive"))
      (node (ref "C10") (pin "1") (pinfunction "1_1") (pintype "passive"))
      (node (ref "C11") (pin "1") (pinfunction "1_1") (pintype "passive"))
      (node (ref "C12") (pin "1") (pinfunction "1_1") (pintype "passive"))
      (node (ref "C13") (pin "1") (pinfunction "1_1") (pintype "passive"))
      (node (ref "C14") (pin "1") (pinfunction "1_1") (pintype "passive"))
      (node (ref "C15") (pin "1") (pinfunction "1_1") (pintype "passive"))
      (node (ref "C16") (pin "1") (pinfunction "1_1") (pintype "passive"))
      (node (ref "C17") (pin "2") (pinfunction "2_2") (pintype "passive"))
      (node (ref "C2") (pin "1") (pinfunction "1_1") (pintype "passive"))
      (node (ref "C3") (pin "1") (pinfunction "1_1") (pintype "passive"))
      (node (ref "C4") (pin "1") (pinfunction "1_1") (pintype "passive"))
      (node (ref "C5") (pin "1") (pinfunction "1_1") (pintype "passive"))
      (node (ref "C6") (pin "1") (pinfunction "1_1") (pintype "passive"))
      (node (ref "C7") (pin "1") (pinfunction "1_1") (pintype "passive"))
      (node (ref "C8") (pin "1") (pinfunction "1_1") (pintype "passive"))
      (node (ref "C9") (pin "1") (pinfunction "1_1") (pintype "passive"))
      (node (ref "CR1") (pin "2") (pinfunction "2_2") (pintype "passive"))
      (node (ref "CR2") (pin "2") (pinfunction "2_2") (pintype "passive"))
      (node (ref "CR3") (pin "1") (pinfunction "1_1") (pintype "passive"))
      (node (ref "CR4") (pin "2") (pinfunction "2_2") (pintype "passive"))
      (node (ref "CR5") (pin "2") (pinfunction "2_2") (pintype "passive"))
      (node (ref "CR6") (pin "1") (pinfunction "1_1") (pintype "passive"))
      (node (ref "D1") (pin "2") (pinfunction "2_2") (pintype "passive"))
      (node (ref "J1") (pin "A1B12") (pinfunction "GND1_A1B12") (pintype "power_in"))
      (node (ref "J1") (pin "B1A12") (pinfunction "GND2_B1A12") (pintype "power_in"))
      (node (ref "J1") (pin "SH1") (pinfunction "SHIELD1_SH1") (pintype "passive"))
      (node (ref "J1") (pin "SH2") (pinfunction "SHIELD2_SH2") (pintype "passive"))
      (node (ref "J1") (pin "SH3") (pinfunction "SHIELD3_SH3") (pintype "passive"))
      (node (ref "J1") (pin "SH4") (pinfunction "SHIELD4_SH4") (pintype "passive"))
      (node (ref "J2") (pin "A1B12") (pinfunction "GND1_A1B12") (pintype "power_in"))
      (node (ref "J2") (pin "B1A12") (pinfunction "GND2_B1A12") (pintype "power_in"))
      (node (ref "J2") (pin "SH1") (pinfunction "SHIELD1_SH1") (pintype "passive"))
      (node (ref "J2") (pin "SH2") (pinfunction "SHIELD2_SH2") (pintype "passive"))
      (node (ref "J2") (pin "SH3") (pinfunction "SHIELD3_SH3") (pintype "passive"))
      (node (ref "J2") (pin "SH4") (pinfunction "SHIELD4_SH4") (pintype "passive"))
      (node (ref "J5") (pin "2") (pinfunction "2_2") (pintype "passive"))
      (node (ref "J5") (pin "24") (pinfunction "24_24") (pintype "passive"))
      (node (ref "J6") (pin "1") (pinfunction "1_1") (pintype "passive"))
      (node (ref "J6") (pin "23") (pinfunction "23_23") (pintype "passive"))
      (node (ref "R11") (pin "1") (pinfunction "1_1") (pintype "passive"))
      (node (ref "R13") (pin "1") (pinfunction "1_1") (pintype "passive"))
      (node (ref "R14") (pin "1") (pinfunction "1_1") (pintype "passive"))
      (node (ref "R22") (pin "2") (pinfunction "2_2") (pintype "passive"))
      (node (ref "R25") (pin "2") (pinfunction "2_2") (pintype "passive"))
      (node (ref "R7") (pin "1") (pinfunction "1_1") (pintype "passive"))
      (node (ref "S1") (pin "3") (pinfunction "3_3") (pintype "passive"))
      (node (ref "S1") (pin "4") (pinfunction "4_4") (pintype "passive"))
      (node (ref "S2") (pin "3") (pinfunction "3_3") (pintype "passive"))
      (node (ref "S2") (pin "4") (pinfunction "4_4") (pintype "passive"))
      (node (ref "U2") (pin "2") (pinfunction "GND_2_2") (pintype "power_in"))
      (node (ref "U2") (pin "4") (pinfunction "GND_4_4") (pintype "power_in"))
      (node (ref "U3") (pin "13") (pinfunction "GND_13") (pintype "passive"))
      (node (ref "U3") (pin "21") (pinfunction "GND_21") (pintype "passive"))
      (node (ref "U3") (pin "3") (pinfunction "GND_3") (pintype "passive"))
    )
    (net (code "62") (name "Net-(D1-Pad1)") (class "Default")
      (node (ref "D1") (pin "1") (pinfunction "1_1") (pintype "passive"))
      (node (ref "R1") (pin "2") (pinfunction "2_2") (pintype "passive"))
    )
    (net (code "63") (name "Net-(D2-Pad1)") (class "Default")
      (node (ref "D2") (pin "1") (pinfunction "1_1") (pintype "passive"))
      (node (ref "R3") (pin "2") (pinfunction "2_2") (pintype "passive"))
    )
    (net (code "64") (name "Net-(J1-CC1)") (class "Default")
      (node (ref "J1") (pin "A5") (pinfunction "CC1_A5") (pintype "bidirectional"))
      (node (ref "R11") (pin "2") (pinfunction "2_2") (pintype "passive"))
    )
    (net (code "65") (name "Net-(J1-CC2)") (class "Default")
      (node (ref "J1") (pin "B5") (pinfunction "CC2_B5") (pintype "bidirectional"))
      (node (ref "R7") (pin "2") (pinfunction "2_2") (pintype "passive"))
    )
    (net (code "66") (name "Net-(J2-CC1)") (class "Default")
      (node (ref "J2") (pin "A5") (pinfunction "CC1_A5") (pintype "bidirectional"))
      (node (ref "R14") (pin "2") (pinfunction "2_2") (pintype "passive"))
    )
    (net (code "67") (name "Net-(J2-CC2)") (class "Default")
      (node (ref "J2") (pin "B5") (pinfunction "CC2_B5") (pintype "bidirectional"))
      (node (ref "R13") (pin "2") (pinfunction "2_2") (pintype "passive"))
    )
    (net (code "68") (name "Net-(Q1-B)") (class "Default")
      (node (ref "Q1") (pin "1") (pinfunction "B_1") (pintype "passive"))
      (node (ref "R16") (pin "2") (pinfunction "2_2") (pintype "passive"))
    )
    (net (code "69") (name "Net-(Q2-B)") (class "Default")
      (node (ref "Q2") (pin "1") (pinfunction "B_1") (pintype "passive"))
      (node (ref "R23") (pin "2") (pinfunction "2_2") (pintype "passive"))
    )
    (net (code "70") (name "Net-(U1-3V3)") (class "Default")
      (node (ref "C1") (pin "1") (pinfunction "1_1") (pintype "passive"))
      (node (ref "C2") (pin "2") (pinfunction "2_2") (pintype "passive"))
      (node (ref "U1") (pin "3") (pinfunction "3V3_3") (pintype "power_in"))
    )
    (net (code "71") (name "Net-(U1-GND-Pad1)") (class "Default")
      (node (ref "U1") (pin "1") (pinfunction "GND_1") (pintype "power_in"))
      (node (ref "U1") (pin "2") (pinfunction "GND_2") (pintype "power_in"))
      (node (ref "U1") (pin "42") (pinfunction "GND_42") (pintype "power_in"))
      (node (ref "U1") (pin "43") (pinfunction "GND_43") (pintype "power_in"))
      (node (ref "U1") (pin "46") (pinfunction "GND_46") (pintype "power_in"))
      (node (ref "U1") (pin "47") (pinfunction "GND_47") (pintype "power_in"))
      (node (ref "U1") (pin "48") (pinfunction "GND_48") (pintype "power_in"))
      (node (ref "U1") (pin "49") (pinfunction "GND_49") (pintype "power_in"))
      (node (ref "U1") (pin "50") (pinfunction "GND_50") (pintype "power_in"))
      (node (ref "U1") (pin "51") (pinfunction "GND_51") (pintype "power_in"))
      (node (ref "U1") (pin "52") (pinfunction "GND_52") (pintype "power_in"))
      (node (ref "U1") (pin "53") (pinfunction "GND_53") (pintype "power_in"))
      (node (ref "U1") (pin "54") (pinfunction "GND_54") (pintype "power_in"))
      (node (ref "U1") (pin "55") (pinfunction "GND_55") (pintype "power_in"))
      (node (ref "U1") (pin "56") (pinfunction "GND_56") (pintype "power_in"))
      (node (ref "U1") (pin "57") (pinfunction "GND_57") (pintype "power_in"))
      (node (ref "U1") (pin "58") (pinfunction "GND_58") (pintype "power_in"))
      (node (ref "U1") (pin "59") (pinfunction "GND_59") (pintype "power_in"))
      (node (ref "U1") (pin "60") (pinfunction "GND_60") (pintype "power_in"))
      (node (ref "U1") (pin "61") (pinfunction "GND_61") (pintype "power_in"))
      (node (ref "U1") (pin "61_1") (pinfunction "GND_61_1") (pintype "power_in"))
      (node (ref "U1") (pin "61_2") (pinfunction "GND_61_2") (pintype "power_in"))
      (node (ref "U1") (pin "61_3") (pinfunction "GND_61_3") (pintype "power_in"))
      (node (ref "U1") (pin "61_4") (pinfunction "GND_61_4") (pintype "power_in"))
      (node (ref "U1") (pin "61_5") (pinfunction "GND_61_5") (pintype "power_in"))
      (node (ref "U1") (pin "61_6") (pinfunction "GND_61_6") (pintype "power_in"))
      (node (ref "U1") (pin "61_7") (pinfunction "GND_61_7") (pintype "power_in"))
      (node (ref "U1") (pin "61_8") (pinfunction "GND_61_8") (pintype "power_in"))
      (node (ref "U1") (pin "62") (pinfunction "GND_62") (pintype "power_in"))
      (node (ref "U1") (pin "63") (pinfunction "GND_63") (pintype "power_in"))
      (node (ref "U1") (pin "64") (pinfunction "GND_64") (pintype "power_in"))
      (node (ref "U1") (pin "65") (pinfunction "GND_65") (pintype "power_in"))
    )
    (net (code "72") (name "Net-(U3-CBUS0)") (class "Default")
      (node (ref "R22") (pin "1") (pinfunction "1_1") (pintype "passive"))
      (node (ref "U3") (pin "15") (pinfunction "CBUS0_15") (pintype "passive"))
    )
    (net (code "73") (name "Net-(U3-RESET#)") (class "Default")
      (node (ref "C12") (pin "2") (pinfunction "2_2") (pintype "passive"))
      (node (ref "R17") (pin "1") (pinfunction "1_1") (pintype "passive"))
      (node (ref "U3") (pin "11") (pinfunction "RESET#_11") (pintype "passive"))
    )
    (net (code "74") (name "Net-(U3-VCC)") (class "Default")
      (node (ref "C11") (pin "2") (pinfunction "2_2") (pintype "passive"))
      (node (ref "C15") (pin "2") (pinfunction "2_2") (pintype "passive"))
      (node (ref "R18") (pin "1") (pinfunction "1_1") (pintype "passive"))
      (node (ref "R21") (pin "1") (pinfunction "1_1") (pintype "passive"))
      (node (ref "U3") (pin "12") (pinfunction "VCC_12") (pintype "passive"))
    )
    (net (code "75") (name "unconnected-(J1-SBU1-PadA8)") (class "Default")
      (node (ref "J1") (pin "A8") (pinfunction "SBU1_A8") (pintype "bidirectional"))
    )
    (net (code "76") (name "unconnected-(J1-SBU2-PadB8)") (class "Default")
      (node (ref "J1") (pin "B8") (pinfunction "SBU2_B8") (pintype "bidirectional+no_connect"))
    )
    (net (code "77") (name "unconnected-(J2-SBU1-PadA8)") (class "Default")
      (node (ref "J2") (pin "A8") (pinfunction "SBU1_A8") (pintype "bidirectional+no_connect"))
    )
    (net (code "78") (name "unconnected-(J2-SBU2-PadB8)") (class "Default")
      (node (ref "J2") (pin "B8") (pinfunction "SBU2_B8") (pintype "bidirectional+no_connect"))
    )
    (net (code "79") (name "unconnected-(J6-Pad24)") (class "Default")
      (node (ref "J6") (pin "24") (pinfunction "24_24") (pintype "passive"))
    )
    (net (code "80") (name "unconnected-(U3-CBUS1-Pad14)") (class "Default")
      (node (ref "U3") (pin "14") (pinfunction "CBUS1_14") (pintype "passive+no_connect"))
    )
    (net (code "81") (name "unconnected-(U3-CBUS2-Pad7)") (class "Default")
      (node (ref "U3") (pin "7") (pinfunction "CBUS2_7") (pintype "passive+no_connect"))
    )
    (net (code "82") (name "unconnected-(U3-CTS#-Pad6)") (class "Default")
      (node (ref "U3") (pin "6") (pinfunction "CTS#_6") (pintype "passive+no_connect"))
    )
    (net (code "83") (name "unconnected-(U3-DCD#-Pad5)") (class "Default")
      (node (ref "U3") (pin "5") (pinfunction "DCD#_5") (pintype "passive+no_connect"))
    )
    (net (code "84") (name "unconnected-(U3-DSR#-Pad4)") (class "Default")
      (node (ref "U3") (pin "4") (pinfunction "DSR#_4") (pintype "passive+no_connect"))
    )
    (net (code "85") (name "unconnected-(U3-RI#-Pad2)") (class "Default")
      (node (ref "U3") (pin "2") (pinfunction "RI#_2") (pintype "passive+no_connect"))
    )
  )
)
